# env.net
KiCad netlist of a schematic drawn in EAGLE
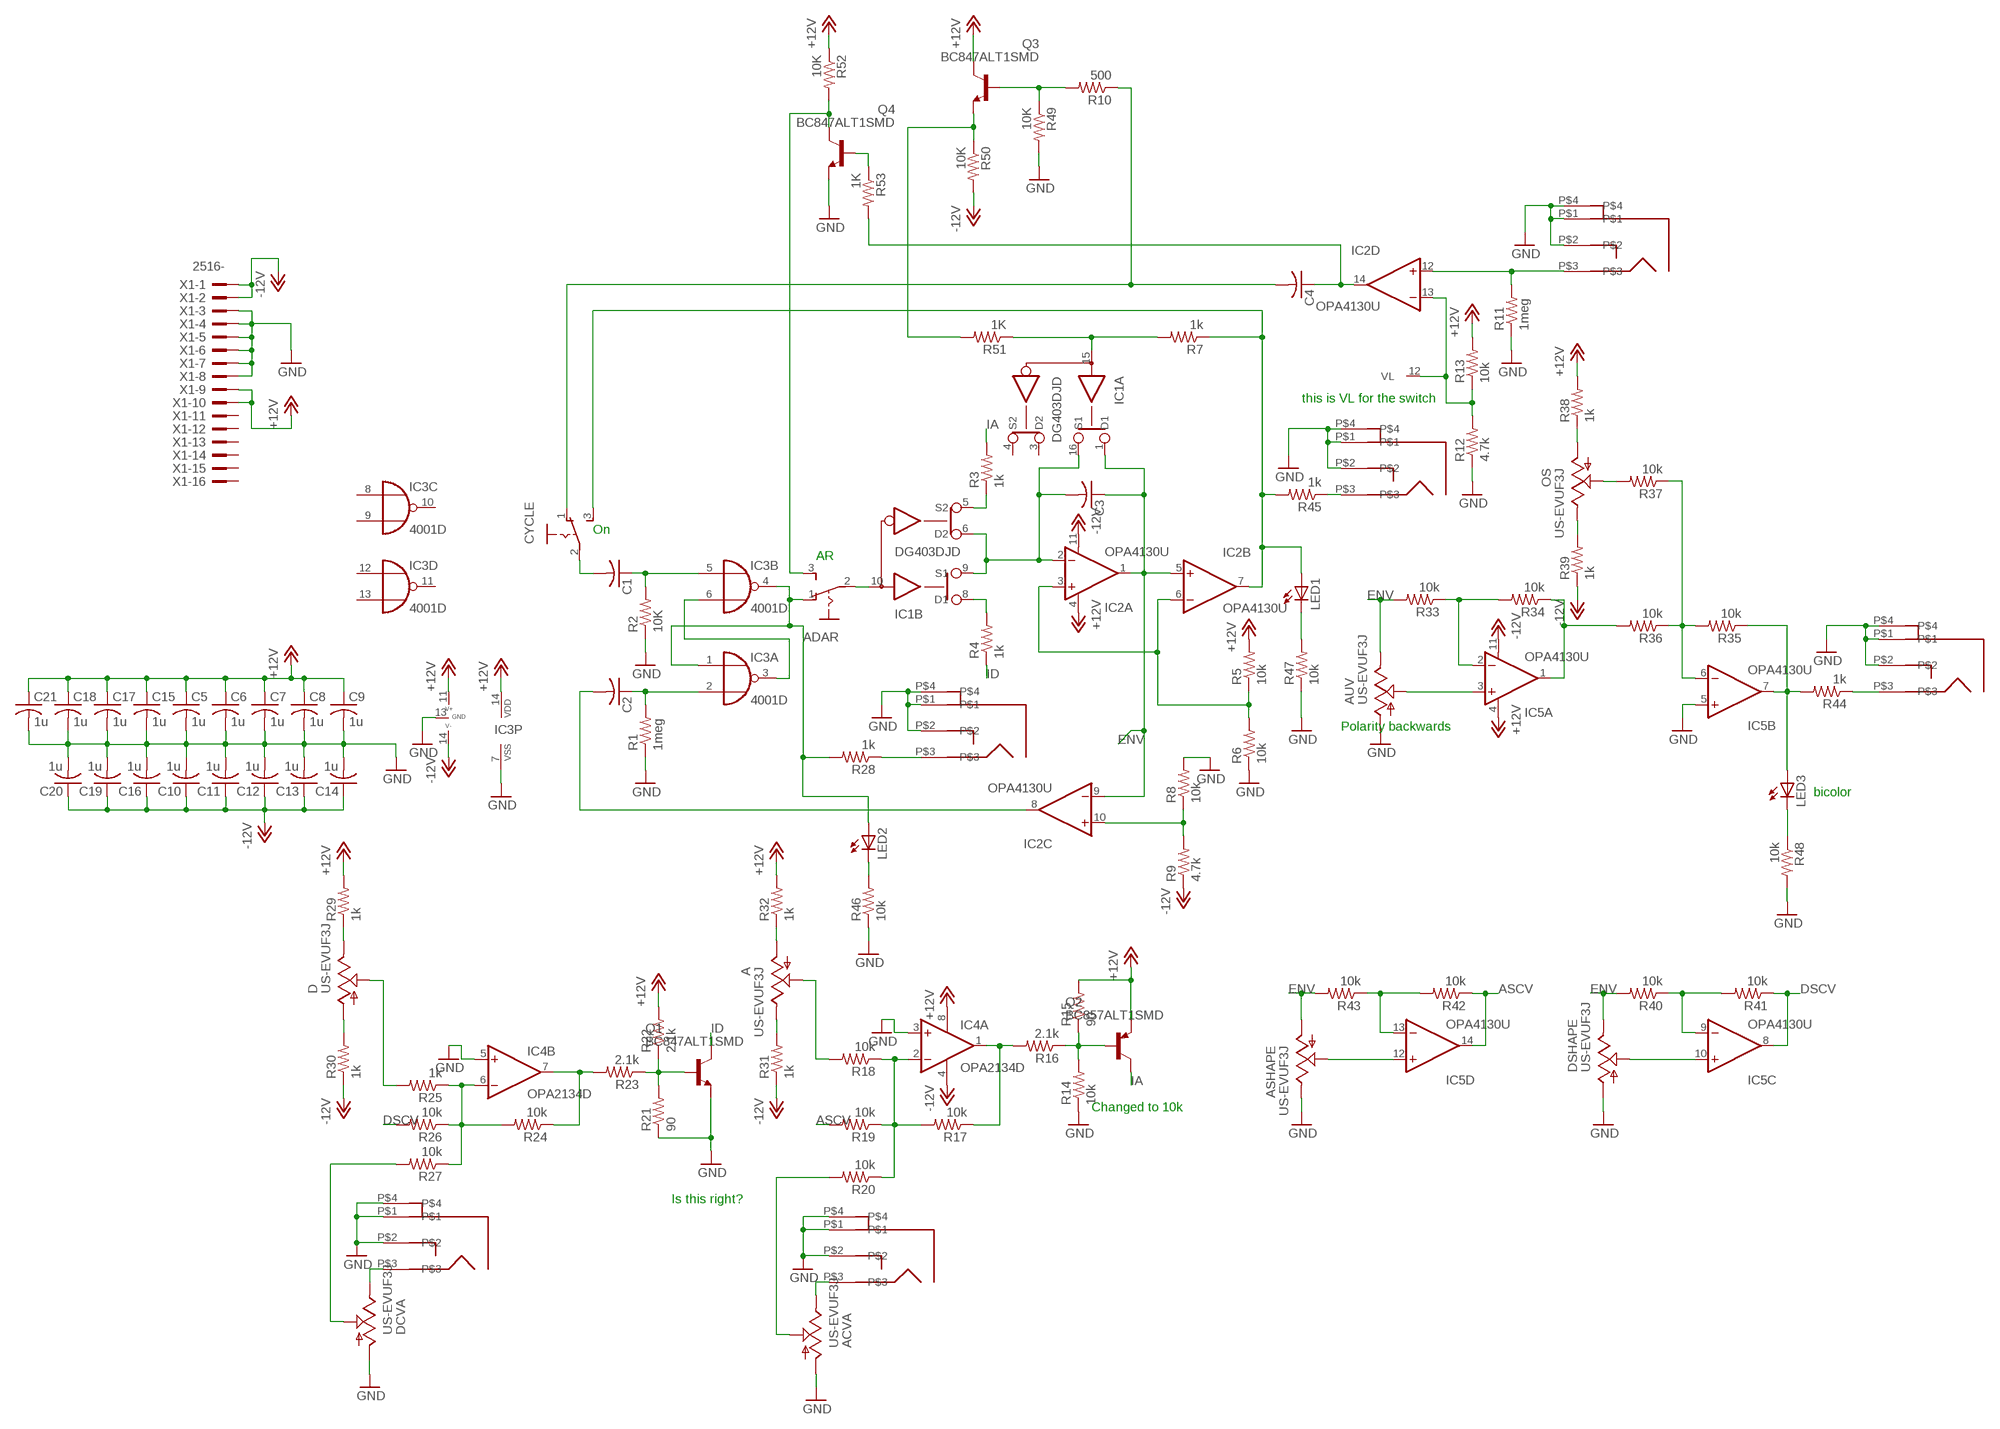
[diagram p0: schematic, sheet 1]

(export (version "E")
  (design (tool "Eeschema 10.0.6"))
  (components
    (comp (ref "A")
      (value "US-EVUF3J")
      (footprint "eagle-import:EVUFXJ")
      (libsource (lib "eagle-import") (part "US-EVUF3J"))
    )
    (comp (ref "ACV")
      (value "PJ301BM")
      (footprint "eagle-import:PJ301BM")
      (libsource (lib "eagle-import") (part "PJ301BM"))
    )
    (comp (ref "ACVA")
      (value "US-EVUF3J")
      (footprint "eagle-import:EVUFXJ")
      (libsource (lib "eagle-import") (part "US-EVUF3J"))
    )
    (comp (ref "ADAR")
      (value "255SB")
      (footprint "eagle-import:255SB")
      (libsource (lib "eagle-import") (part "255SB"))
    )
    (comp (ref "ASHAPE")
      (value "US-EVUF3J")
      (footprint "eagle-import:EVUFXJ")
      (libsource (lib "eagle-import") (part "US-EVUF3J"))
    )
    (comp (ref "AUV")
      (value "US-EVUF3J")
      (footprint "eagle-import:EVUFXJ")
      (libsource (lib "eagle-import") (part "US-EVUF3J"))
    )
    (comp (ref "C1")
      (value "C-USC0603")
      (footprint "eagle-import:C0603")
      (libsource (lib "eagle-import") (part "C-USC0603"))
    )
    (comp (ref "C2")
      (value "C-USC0603")
      (footprint "eagle-import:C0603")
      (libsource (lib "eagle-import") (part "C-USC0603"))
    )
    (comp (ref "C3")
      (value "C-USC0603")
      (footprint "eagle-import:C0603")
      (libsource (lib "eagle-import") (part "C-USC0603"))
    )
    (comp (ref "C4")
      (value "C-USC0603")
      (footprint "eagle-import:C0603")
      (libsource (lib "eagle-import") (part "C-USC0603"))
    )
    (comp (ref "C5")
      (value "1u")
      (footprint "eagle-import:C0603")
      (libsource (lib "eagle-import") (part "C-USC0603"))
    )
    (comp (ref "C6")
      (value "1u")
      (footprint "eagle-import:C0603")
      (libsource (lib "eagle-import") (part "C-USC0603"))
    )
    (comp (ref "C7")
      (value "1u")
      (footprint "eagle-import:C0603")
      (libsource (lib "eagle-import") (part "C-USC0603"))
    )
    (comp (ref "C8")
      (value "1u")
      (footprint "eagle-import:C0603")
      (libsource (lib "eagle-import") (part "C-USC0603"))
    )
    (comp (ref "C9")
      (value "1u")
      (footprint "eagle-import:C0603")
      (libsource (lib "eagle-import") (part "C-USC0603"))
    )
    (comp (ref "C10")
      (value "1u")
      (footprint "eagle-import:C0603")
      (libsource (lib "eagle-import") (part "C-USC0603"))
    )
    (comp (ref "C11")
      (value "1u")
      (footprint "eagle-import:C0603")
      (libsource (lib "eagle-import") (part "C-USC0603"))
    )
    (comp (ref "C12")
      (value "1u")
      (footprint "eagle-import:C0603")
      (libsource (lib "eagle-import") (part "C-USC0603"))
    )
    (comp (ref "C13")
      (value "1u")
      (footprint "eagle-import:C0603")
      (libsource (lib "eagle-import") (part "C-USC0603"))
    )
    (comp (ref "C14")
      (value "1u")
      (footprint "eagle-import:C0603")
      (libsource (lib "eagle-import") (part "C-USC0603"))
    )
    (comp (ref "C15")
      (value "1u")
      (footprint "eagle-import:C0603")
      (libsource (lib "eagle-import") (part "C-USC0603"))
    )
    (comp (ref "C16")
      (value "1u")
      (footprint "eagle-import:C0603")
      (libsource (lib "eagle-import") (part "C-USC0603"))
    )
    (comp (ref "C17")
      (value "1u")
      (footprint "eagle-import:C0603")
      (libsource (lib "eagle-import") (part "C-USC0603"))
    )
    (comp (ref "C18")
      (value "1u")
      (footprint "eagle-import:C0603")
      (libsource (lib "eagle-import") (part "C-USC0603"))
    )
    (comp (ref "C19")
      (value "1u")
      (footprint "eagle-import:C0603")
      (libsource (lib "eagle-import") (part "C-USC0603"))
    )
    (comp (ref "C20")
      (value "1u")
      (footprint "eagle-import:C0603")
      (libsource (lib "eagle-import") (part "C-USC0603"))
    )
    (comp (ref "C21")
      (value "1u")
      (footprint "eagle-import:C0603")
      (libsource (lib "eagle-import") (part "C-USC0603"))
    )
    (comp (ref "CVOUT")
      (value "PJ301BM")
      (footprint "eagle-import:PJ301BM")
      (libsource (lib "eagle-import") (part "PJ301BM"))
    )
    (comp (ref "CYCLE")
      (value "255SB")
      (footprint "eagle-import:255SB")
      (libsource (lib "eagle-import") (part "255SB"))
    )
    (comp (ref "D")
      (value "US-EVUF3J")
      (footprint "eagle-import:EVUFXJ")
      (libsource (lib "eagle-import") (part "US-EVUF3J"))
    )
    (comp (ref "DCV")
      (value "PJ301BM")
      (footprint "eagle-import:PJ301BM")
      (libsource (lib "eagle-import") (part "PJ301BM"))
    )
    (comp (ref "DCVA")
      (value "US-EVUF3J")
      (footprint "eagle-import:EVUFXJ")
      (libsource (lib "eagle-import") (part "US-EVUF3J"))
    )
    (comp (ref "DSHAPE")
      (value "US-EVUF3J")
      (footprint "eagle-import:EVUFXJ")
      (libsource (lib "eagle-import") (part "US-EVUF3J"))
    )
    (comp (ref "EOF")
      (value "PJ301BM")
      (footprint "eagle-import:PJ301BM")
      (libsource (lib "eagle-import") (part "PJ301BM"))
    )
    (comp (ref "EOR")
      (value "PJ301BM")
      (footprint "eagle-import:PJ301BM")
      (libsource (lib "eagle-import") (part "PJ301BM"))
    )
    (comp (ref "GATE")
      (value "PJ301BM")
      (footprint "eagle-import:PJ301BM")
      (libsource (lib "eagle-import") (part "PJ301BM"))
    )
    (comp (ref "IC1")
      (value "DG403DJD")
      (footprint "eagle-import:SO16")
      (libsource (lib "eagle-import") (part "DG403DJD"))
    )
    (comp (ref "IC2")
      (value "OPA4130U")
      (footprint "eagle-import:SO14")
      (fields (field (name "MF") "TEXAS INSTRUMENTS") (field (name "MPN") "OPA4130UA"))
      (libsource (lib "eagle-import") (part "OPA4130U"))
    )
    (comp (ref "IC3")
      (value "4001D")
      (footprint "eagle-import:SO14")
      (libsource (lib "eagle-import") (part "4001D"))
    )
    (comp (ref "IC4")
      (value "OPA2134D")
      (footprint "eagle-import:SOIC8")
      (libsource (lib "eagle-import") (part "OPA2134D"))
    )
    (comp (ref "IC5")
      (value "OPA4130U")
      (footprint "eagle-import:SO14")
      (fields (field (name "MF") "TEXAS INSTRUMENTS") (field (name "MPN") "OPA4130UA"))
      (libsource (lib "eagle-import") (part "OPA4130U"))
    )
    (comp (ref "LED1")
      (value "LED5MM")
      (footprint "eagle-import:LED5MM")
      (libsource (lib "eagle-import") (part "LED5MM"))
    )
    (comp (ref "LED2")
      (value "LED5MM")
      (footprint "eagle-import:LED5MM")
      (libsource (lib "eagle-import") (part "LED5MM"))
    )
    (comp (ref "LED3")
      (value "LED5MM")
      (footprint "eagle-import:LED5MM")
      (libsource (lib "eagle-import") (part "LED5MM"))
    )
    (comp (ref "OS")
      (value "US-EVUF3J")
      (footprint "eagle-import:EVUFXJ")
      (libsource (lib "eagle-import") (part "US-EVUF3J"))
    )
    (comp (ref "Q1")
      (value "BC847ALT1SMD")
      (footprint "eagle-import:SOT23")
      (libsource (lib "eagle-import") (part "BC847SMDALT1"))
    )
    (comp (ref "Q2")
      (value "BC857ALT1SMD")
      (footprint "eagle-import:SOT23-BEC")
      (libsource (lib "eagle-import") (part "BC857SMDALT1"))
    )
    (comp (ref "Q3")
      (value "BC847ALT1SMD")
      (footprint "eagle-import:SOT23")
      (libsource (lib "eagle-import") (part "BC847SMDALT1"))
    )
    (comp (ref "Q4")
      (value "BC847ALT1SMD")
      (footprint "eagle-import:SOT23")
      (libsource (lib "eagle-import") (part "BC847SMDALT1"))
    )
    (comp (ref "R1")
      (value "1meg")
      (footprint "eagle-import:R0603")
      (libsource (lib "eagle-import") (part "R-US_R0603"))
    )
    (comp (ref "R2")
      (value "10K")
      (footprint "eagle-import:R0603")
      (libsource (lib "eagle-import") (part "R-US_R0603"))
    )
    (comp (ref "R3")
      (value "1k")
      (footprint "eagle-import:R0603")
      (libsource (lib "eagle-import") (part "R-US_R0603"))
    )
    (comp (ref "R4")
      (value "1k")
      (footprint "eagle-import:R0603")
      (libsource (lib "eagle-import") (part "R-US_R0603"))
    )
    (comp (ref "R5")
      (value "10k")
      (footprint "eagle-import:R0603")
      (libsource (lib "eagle-import") (part "R-US_R0603"))
    )
    (comp (ref "R6")
      (value "10k")
      (footprint "eagle-import:R0603")
      (libsource (lib "eagle-import") (part "R-US_R0603"))
    )
    (comp (ref "R7")
      (value "1k")
      (footprint "eagle-import:R0603")
      (libsource (lib "eagle-import") (part "R-US_R0603"))
    )
    (comp (ref "R8")
      (value "10k")
      (footprint "eagle-import:R0603")
      (libsource (lib "eagle-import") (part "R-US_R0603"))
    )
    (comp (ref "R9")
      (value "4.7k")
      (footprint "eagle-import:R0603")
      (libsource (lib "eagle-import") (part "R-US_R0603"))
    )
    (comp (ref "R10")
      (value "500")
      (footprint "eagle-import:R0603")
      (libsource (lib "eagle-import") (part "R-US_R0603"))
    )
    (comp (ref "R11")
      (value "1meg")
      (footprint "eagle-import:R0603")
      (libsource (lib "eagle-import") (part "R-US_R0603"))
    )
    (comp (ref "R12")
      (value "4.7k")
      (footprint "eagle-import:R0603")
      (libsource (lib "eagle-import") (part "R-US_R0603"))
    )
    (comp (ref "R13")
      (value "10k")
      (footprint "eagle-import:R0603")
      (libsource (lib "eagle-import") (part "R-US_R0603"))
    )
    (comp (ref "R14")
      (value "10k")
      (footprint "eagle-import:R0603")
      (libsource (lib "eagle-import") (part "R-US_R0603"))
    )
    (comp (ref "R15")
      (value "90")
      (footprint "eagle-import:R0603")
      (libsource (lib "eagle-import") (part "R-US_R0603"))
    )
    (comp (ref "R16")
      (value "2.1k")
      (footprint "eagle-import:R0603")
      (libsource (lib "eagle-import") (part "R-US_R0603"))
    )
    (comp (ref "R17")
      (value "10k")
      (footprint "eagle-import:R0603")
      (libsource (lib "eagle-import") (part "R-US_R0603"))
    )
    (comp (ref "R18")
      (value "10k")
      (footprint "eagle-import:R0603")
      (libsource (lib "eagle-import") (part "R-US_R0603"))
    )
    (comp (ref "R19")
      (value "10k")
      (footprint "eagle-import:R0603")
      (libsource (lib "eagle-import") (part "R-US_R0603"))
    )
    (comp (ref "R20")
      (value "10k")
      (footprint "eagle-import:R0603")
      (libsource (lib "eagle-import") (part "R-US_R0603"))
    )
    (comp (ref "R21")
      (value "90")
      (footprint "eagle-import:R0603")
      (libsource (lib "eagle-import") (part "R-US_R0603"))
    )
    (comp (ref "R22")
      (value "2.1k")
      (footprint "eagle-import:R0603")
      (libsource (lib "eagle-import") (part "R-US_R0603"))
    )
    (comp (ref "R23")
      (value "2.1k")
      (footprint "eagle-import:R0603")
      (libsource (lib "eagle-import") (part "R-US_R0603"))
    )
    (comp (ref "R24")
      (value "10k")
      (footprint "eagle-import:R0603")
      (libsource (lib "eagle-import") (part "R-US_R0603"))
    )
    (comp (ref "R25")
      (value "1k")
      (footprint "eagle-import:R0603")
      (libsource (lib "eagle-import") (part "R-US_R0603"))
    )
    (comp (ref "R26")
      (value "10k")
      (footprint "eagle-import:R0603")
      (libsource (lib "eagle-import") (part "R-US_R0603"))
    )
    (comp (ref "R27")
      (value "10k")
      (footprint "eagle-import:R0603")
      (libsource (lib "eagle-import") (part "R-US_R0603"))
    )
    (comp (ref "R28")
      (value "1k")
      (footprint "eagle-import:R0603")
      (libsource (lib "eagle-import") (part "R-US_R0603"))
    )
    (comp (ref "R29")
      (value "1k")
      (footprint "eagle-import:R0603")
      (libsource (lib "eagle-import") (part "R-US_R0603"))
    )
    (comp (ref "R30")
      (value "1k")
      (footprint "eagle-import:R0603")
      (libsource (lib "eagle-import") (part "R-US_R0603"))
    )
    (comp (ref "R31")
      (value "1k")
      (footprint "eagle-import:R0603")
      (libsource (lib "eagle-import") (part "R-US_R0603"))
    )
    (comp (ref "R32")
      (value "1k")
      (footprint "eagle-import:R0603")
      (libsource (lib "eagle-import") (part "R-US_R0603"))
    )
    (comp (ref "R33")
      (value "10k")
      (footprint "eagle-import:R0603")
      (libsource (lib "eagle-import") (part "R-US_R0603"))
    )
    (comp (ref "R34")
      (value "10k")
      (footprint "eagle-import:R0603")
      (libsource (lib "eagle-import") (part "R-US_R0603"))
    )
    (comp (ref "R35")
      (value "10k")
      (footprint "eagle-import:R0603")
      (libsource (lib "eagle-import") (part "R-US_R0603"))
    )
    (comp (ref "R36")
      (value "10k")
      (footprint "eagle-import:R0603")
      (libsource (lib "eagle-import") (part "R-US_R0603"))
    )
    (comp (ref "R37")
      (value "10k")
      (footprint "eagle-import:R0603")
      (libsource (lib "eagle-import") (part "R-US_R0603"))
    )
    (comp (ref "R38")
      (value "1k")
      (footprint "eagle-import:R0603")
      (libsource (lib "eagle-import") (part "R-US_R0603"))
    )
    (comp (ref "R39")
      (value "1k")
      (footprint "eagle-import:R0603")
      (libsource (lib "eagle-import") (part "R-US_R0603"))
    )
    (comp (ref "R40")
      (value "10k")
      (footprint "eagle-import:R0603")
      (libsource (lib "eagle-import") (part "R-US_R0603"))
    )
    (comp (ref "R41")
      (value "10k")
      (footprint "eagle-import:R0603")
      (libsource (lib "eagle-import") (part "R-US_R0603"))
    )
    (comp (ref "R42")
      (value "10k")
      (footprint "eagle-import:R0603")
      (libsource (lib "eagle-import") (part "R-US_R0603"))
    )
    (comp (ref "R43")
      (value "10k")
      (footprint "eagle-import:R0603")
      (libsource (lib "eagle-import") (part "R-US_R0603"))
    )
    (comp (ref "R44")
      (value "1k")
      (footprint "eagle-import:R0603")
      (libsource (lib "eagle-import") (part "R-US_R0603"))
    )
    (comp (ref "R45")
      (value "1k")
      (footprint "eagle-import:R0603")
      (libsource (lib "eagle-import") (part "R-US_R0603"))
    )
    (comp (ref "R46")
      (value "10k")
      (footprint "eagle-import:R0603")
      (libsource (lib "eagle-import") (part "R-US_R0603"))
    )
    (comp (ref "R47")
      (value "10k")
      (footprint "eagle-import:R0603")
      (libsource (lib "eagle-import") (part "R-US_R0603"))
    )
    (comp (ref "R48")
      (value "10k")
      (footprint "eagle-import:R0603")
      (libsource (lib "eagle-import") (part "R-US_R0603"))
    )
    (comp (ref "R49")
      (value "10K")
      (footprint "eagle-import:R0603")
      (libsource (lib "eagle-import") (part "R-US_R0603"))
    )
    (comp (ref "R50")
      (value "10K")
      (footprint "eagle-import:R0603")
      (libsource (lib "eagle-import") (part "R-US_R0603"))
    )
    (comp (ref "R51")
      (value "1K")
      (footprint "eagle-import:R0603")
      (libsource (lib "eagle-import") (part "R-US_R0603"))
    )
    (comp (ref "R52")
      (value "10K")
      (footprint "eagle-import:R0603")
      (libsource (lib "eagle-import") (part "R-US_R0603"))
    )
    (comp (ref "R53")
      (value "1K")
      (footprint "eagle-import:R0603")
      (libsource (lib "eagle-import") (part "R-US_R0603"))
    )
    (comp (ref "X1")
      (value "2516-")
      (footprint "eagle-import:PAK100_2500-16")
      (libsource (lib "eagle-import") (part "2516-"))
    )
  )
  (nets
    (net (code "1") (name "+12V") (class "Default")
      (node (ref "C15") (pin "1") (pinfunction "1_1") (pintype "passive"))
      (node (ref "C17") (pin "1") (pinfunction "1_1") (pintype "passive"))
      (node (ref "C18") (pin "1") (pinfunction "1_1") (pintype "passive"))
      (node (ref "C21") (pin "1") (pinfunction "1_1") (pintype "passive"))
      (node (ref "C5") (pin "1") (pinfunction "1_1") (pintype "passive"))
      (node (ref "C6") (pin "1") (pinfunction "1_1") (pintype "passive"))
      (node (ref "C7") (pin "1") (pinfunction "1_1") (pintype "passive"))
      (node (ref "C8") (pin "1") (pinfunction "1_1") (pintype "passive"))
      (node (ref "C9") (pin "1") (pinfunction "1_1") (pintype "passive"))
      (node (ref "IC1") (pin "11") (pinfunction "V+_11") (pintype "power_in"))
      (node (ref "IC2") (pin "4") (pinfunction "V+_4") (pintype "power_in"))
      (node (ref "IC3") (pin "14") (pinfunction "VDD_14") (pintype "power_in"))
      (node (ref "IC4") (pin "8") (pinfunction "V+_8") (pintype "power_in"))
      (node (ref "IC5") (pin "4") (pinfunction "V+_4") (pintype "power_in"))
      (node (ref "Q2") (pin "E") (pinfunction "E_E") (pintype "passive"))
      (node (ref "Q3") (pin "3") (pinfunction "C_3") (pintype "passive"))
      (node (ref "R13") (pin "2") (pinfunction "2_2") (pintype "passive"))
      (node (ref "R15") (pin "2") (pinfunction "2_2") (pintype "passive"))
      (node (ref "R22") (pin "2") (pinfunction "2_2") (pintype "passive"))
      (node (ref "R29") (pin "2") (pinfunction "2_2") (pintype "passive"))
      (node (ref "R32") (pin "2") (pinfunction "2_2") (pintype "passive"))
      (node (ref "R38") (pin "2") (pinfunction "2_2") (pintype "passive"))
      (node (ref "R5") (pin "2") (pinfunction "2_2") (pintype "passive"))
      (node (ref "R52") (pin "1") (pinfunction "1_1") (pintype "passive"))
      (node (ref "X1") (pin "10") (pinfunction "KL_10") (pintype "passive"))
      (node (ref "X1") (pin "9") (pinfunction "KL_9") (pintype "passive"))
    )
    (net (code "2") (name "-12V") (class "Default")
      (node (ref "C10") (pin "1") (pinfunction "1_1") (pintype "passive"))
      (node (ref "C11") (pin "1") (pinfunction "1_1") (pintype "passive"))
      (node (ref "C12") (pin "1") (pinfunction "1_1") (pintype "passive"))
      (node (ref "C13") (pin "1") (pinfunction "1_1") (pintype "passive"))
      (node (ref "C14") (pin "1") (pinfunction "1_1") (pintype "passive"))
      (node (ref "C16") (pin "1") (pinfunction "1_1") (pintype "passive"))
      (node (ref "C19") (pin "1") (pinfunction "1_1") (pintype "passive"))
      (node (ref "C20") (pin "1") (pinfunction "1_1") (pintype "passive"))
      (node (ref "IC1") (pin "14") (pinfunction "V-_14") (pintype "power_in"))
      (node (ref "IC2") (pin "11") (pinfunction "V-_11") (pintype "power_in"))
      (node (ref "IC4") (pin "4") (pinfunction "V-_4") (pintype "power_in"))
      (node (ref "IC5") (pin "11") (pinfunction "V-_11") (pintype "power_in"))
      (node (ref "R30") (pin "1") (pinfunction "1_1") (pintype "passive"))
      (node (ref "R31") (pin "1") (pinfunction "1_1") (pintype "passive"))
      (node (ref "R39") (pin "1") (pinfunction "1_1") (pintype "passive"))
      (node (ref "R50") (pin "2") (pinfunction "2_2") (pintype "passive"))
      (node (ref "R9") (pin "1") (pinfunction "1_1") (pintype "passive"))
      (node (ref "X1") (pin "1") (pinfunction "KL_1") (pintype "passive"))
      (node (ref "X1") (pin "2") (pinfunction "KL_2") (pintype "passive"))
    )
    (net (code "3") (name "/ASCV") (class "Default")
      (node (ref "IC5") (pin "14") (pinfunction "OUT_14") (pintype "output"))
      (node (ref "R19") (pin "2") (pinfunction "2_2") (pintype "passive"))
      (node (ref "R42") (pin "1") (pinfunction "1_1") (pintype "passive"))
    )
    (net (code "4") (name "/DSCV") (class "Default")
      (node (ref "IC5") (pin "8") (pinfunction "OUT_8") (pintype "output"))
      (node (ref "R26") (pin "2") (pinfunction "2_2") (pintype "passive"))
      (node (ref "R41") (pin "1") (pinfunction "1_1") (pintype "passive"))
    )
    (net (code "5") (name "/ENV") (class "Default")
      (node (ref "ASHAPE") (pin "1") (pinfunction "A_1") (pintype "passive"))
      (node (ref "AUV") (pin "3") (pinfunction "E_3") (pintype "passive"))
      (node (ref "C3") (pin "1") (pinfunction "1_1") (pintype "passive"))
      (node (ref "DSHAPE") (pin "3") (pinfunction "E_3") (pintype "passive"))
      (node (ref "IC1") (pin "1") (pinfunction "D1_1") (pintype "bidirectional"))
      (node (ref "IC2") (pin "1") (pinfunction "OUT_1") (pintype "output"))
      (node (ref "IC2") (pin "5") (pinfunction "+IN_5") (pintype "input"))
      (node (ref "IC2") (pin "9") (pinfunction "-IN_9") (pintype "input"))
      (node (ref "R33") (pin "2") (pinfunction "2_2") (pintype "passive"))
      (node (ref "R40") (pin "2") (pinfunction "2_2") (pintype "passive"))
      (node (ref "R43") (pin "2") (pinfunction "2_2") (pintype "passive"))
    )
    (net (code "6") (name "/IA") (class "Default")
      (node (ref "Q2") (pin "C") (pinfunction "C_C") (pintype "passive"))
      (node (ref "R3") (pin "2") (pinfunction "2_2") (pintype "passive"))
    )
    (net (code "7") (name "/ID") (class "Default")
      (node (ref "Q1") (pin "3") (pinfunction "C_3") (pintype "passive"))
      (node (ref "R4") (pin "1") (pinfunction "1_1") (pintype "passive"))
    )
    (net (code "8") (name "GND") (class "Default")
      (node (ref "ACV") (pin "P$1") (pinfunction "P$1_P$1") (pintype "bidirectional"))
      (node (ref "ACV") (pin "P$2") (pinfunction "P$2_P$2") (pintype "bidirectional"))
      (node (ref "ACV") (pin "P$4") (pinfunction "P$4_P$4") (pintype "bidirectional"))
      (node (ref "ACVA") (pin "1") (pinfunction "A_1") (pintype "passive"))
      (node (ref "ASHAPE") (pin "3") (pinfunction "E_3") (pintype "passive"))
      (node (ref "AUV") (pin "1") (pinfunction "A_1") (pintype "passive"))
      (node (ref "C10") (pin "2") (pinfunction "2_2") (pintype "passive"))
      (node (ref "C11") (pin "2") (pinfunction "2_2") (pintype "passive"))
      (node (ref "C12") (pin "2") (pinfunction "2_2") (pintype "passive"))
      (node (ref "C13") (pin "2") (pinfunction "2_2") (pintype "passive"))
      (node (ref "C14") (pin "2") (pinfunction "2_2") (pintype "passive"))
      (node (ref "C15") (pin "2") (pinfunction "2_2") (pintype "passive"))
      (node (ref "C16") (pin "2") (pinfunction "2_2") (pintype "passive"))
      (node (ref "C17") (pin "2") (pinfunction "2_2") (pintype "passive"))
      (node (ref "C18") (pin "2") (pinfunction "2_2") (pintype "passive"))
      (node (ref "C19") (pin "2") (pinfunction "2_2") (pintype "passive"))
      (node (ref "C20") (pin "2") (pinfunction "2_2") (pintype "passive"))
      (node (ref "C21") (pin "2") (pinfunction "2_2") (pintype "passive"))
      (node (ref "C5") (pin "2") (pinfunction "2_2") (pintype "passive"))
      (node (ref "C6") (pin "2") (pinfunction "2_2") (pintype "passive"))
      (node (ref "C7") (pin "2") (pinfunction "2_2") (pintype "passive"))
      (node (ref "C8") (pin "2") (pinfunction "2_2") (pintype "passive"))
      (node (ref "C9") (pin "2") (pinfunction "2_2") (pintype "passive"))
      (node (ref "CVOUT") (pin "P$1") (pinfunction "P$1_P$1") (pintype "bidirectional"))
      (node (ref "CVOUT") (pin "P$2") (pinfunction "P$2_P$2") (pintype "bidirectional"))
      (node (ref "CVOUT") (pin "P$4") (pinfunction "P$4_P$4") (pintype "bidirectional"))
      (node (ref "DCV") (pin "P$1") (pinfunction "P$1_P$1") (pintype "bidirectional"))
      (node (ref "DCV") (pin "P$2") (pinfunction "P$2_P$2") (pintype "bidirectional"))
      (node (ref "DCV") (pin "P$4") (pinfunction "P$4_P$4") (pintype "bidirectional"))
      (node (ref "DCVA") (pin "1") (pinfunction "A_1") (pintype "passive"))
      (node (ref "DSHAPE") (pin "1") (pinfunction "A_1") (pintype "passive"))
      (node (ref "EOF") (pin "P$1") (pinfunction "P$1_P$1") (pintype "bidirectional"))
      (node (ref "EOF") (pin "P$2") (pinfunction "P$2_P$2") (pintype "bidirectional"))
      (node (ref "EOF") (pin "P$4") (pinfunction "P$4_P$4") (pintype "bidirectional"))
      (node (ref "EOR") (pin "P$1") (pinfunction "P$1_P$1") (pintype "bidirectional"))
      (node (ref "EOR") (pin "P$2") (pinfunction "P$2_P$2") (pintype "bidirectional"))
      (node (ref "EOR") (pin "P$4") (pinfunction "P$4_P$4") (pintype "bidirectional"))
      (node (ref "GATE") (pin "P$1") (pinfunction "P$1_P$1") (pintype "bidirectional"))
      (node (ref "GATE") (pin "P$2") (pinfunction "P$2_P$2") (pintype "bidirectional"))
      (node (ref "GATE") (pin "P$4") (pinfunction "P$4_P$4") (pintype "bidirectional"))
      (node (ref "IC1") (pin "13") (pinfunction "GND_13") (pintype "power_in"))
      (node (ref "IC3") (pin "7") (pinfunction "VSS_7") (pintype "power_in"))
      (node (ref "IC4") (pin "3") (pinfunction "+IN_3") (pintype "input"))
      (node (ref "IC4") (pin "5") (pinfunction "+IN_5") (pintype "input"))
      (node (ref "IC5") (pin "5") (pinfunction "+IN_5") (pintype "input"))
      (node (ref "Q1") (pin "2") (pinfunction "E_2") (pintype "passive"))
      (node (ref "Q4") (pin "2") (pinfunction "E_2") (pintype "passive"))
      (node (ref "R1") (pin "1") (pinfunction "1_1") (pintype "passive"))
      (node (ref "R11") (pin "1") (pinfunction "1_1") (pintype "passive"))
      (node (ref "R12") (pin "1") (pinfunction "1_1") (pintype "passive"))
      (node (ref "R14") (pin "1") (pinfunction "1_1") (pintype "passive"))
      (node (ref "R2") (pin "1") (pinfunction "1_1") (pintype "passive"))
      (node (ref "R21") (pin "1") (pinfunction "1_1") (pintype "passive"))
      (node (ref "R46") (pin "1") (pinfunction "1_1") (pintype "passive"))
      (node (ref "R47") (pin "1") (pinfunction "1_1") (pintype "passive"))
      (node (ref "R48") (pin "2") (pinfunction "2_2") (pintype "passive"))
      (node (ref "R49") (pin "2") (pinfunction "2_2") (pintype "passive"))
      (node (ref "R6") (pin "1") (pinfunction "1_1") (pintype "passive"))
      (node (ref "R8") (pin "2") (pinfunction "2_2") (pintype "passive"))
      (node (ref "X1") (pin "3") (pinfunction "KL_3") (pintype "passive"))
      (node (ref "X1") (pin "4") (pinfunction "KL_4") (pintype "passive"))
      (node (ref "X1") (pin "5") (pinfunction "KL_5") (pintype "passive"))
      (node (ref "X1") (pin "6") (pinfunction "KL_6") (pintype "passive"))
      (node (ref "X1") (pin "7") (pinfunction "KL_7") (pintype "passive"))
      (node (ref "X1") (pin "8") (pinfunction "KL_8") (pintype "passive"))
    )
    (net (code "9") (name "Net-(A-A)") (class "Default")
      (node (ref "A") (pin "1") (pinfunction "A_1") (pintype "passive"))
      (node (ref "R32") (pin "1") (pinfunction "1_1") (pintype "passive"))
    )
    (net (code "10") (name "Net-(A-E)") (class "Default")
      (node (ref "A") (pin "3") (pinfunction "E_3") (pintype "passive"))
      (node (ref "R31") (pin "2") (pinfunction "2_2") (pintype "passive"))
    )
    (net (code "11") (name "Net-(A-S)") (class "Default")
      (node (ref "A") (pin "2") (pinfunction "S_2") (pintype "passive"))
      (node (ref "R18") (pin "2") (pinfunction "2_2") (pintype "passive"))
    )
    (net (code "12") (name "Net-(ACVA-E)") (class "Default")
      (node (ref "ACV") (pin "P$3") (pinfunction "P$3_P$3") (pintype "bidirectional"))
      (node (ref "ACVA") (pin "3") (pinfunction "E_3") (pintype "passive"))
    )
    (net (code "13") (name "Net-(ACVA-S)") (class "Default")
      (node (ref "ACVA") (pin "2") (pinfunction "S_2") (pintype "passive"))
      (node (ref "R20") (pin "2") (pinfunction "2_2") (pintype "passive"))
    )
    (net (code "14") (name "Net-(ADAR-O)") (class "Default")
      (node (ref "ADAR") (pin "1") (pinfunction "O_1") (pintype "passive"))
      (node (ref "IC3") (pin "1") (pinfunction "I0_1") (pintype "input"))
      (node (ref "IC3") (pin "4") (pinfunction "O_4") (pintype "output"))
      (node (ref "LED2") (pin "A") (pinfunction "A_A") (pintype "passive"))
      (node (ref "R28") (pin "2") (pinfunction "2_2") (pintype "passive"))
    )
    (net (code "15") (name "Net-(ADAR-P)") (class "Default")
      (node (ref "ADAR") (pin "2") (pinfunction "P_2") (pintype "passive"))
      (node (ref "IC1") (pin "10") (pinfunction "IN_10") (pintype "input"))
    )
    (net (code "16") (name "Net-(ADAR-S)") (class "Default")
      (node (ref "ADAR") (pin "3") (pinfunction "S_3") (pintype "passive"))
      (node (ref "Q4") (pin "3") (pinfunction "C_3") (pintype "passive"))
      (node (ref "R52") (pin "2") (pinfunction "2_2") (pintype "passive"))
    )
    (net (code "17") (name "Net-(ASHAPE-S)") (class "Default")
      (node (ref "ASHAPE") (pin "2") (pinfunction "S_2") (pintype "passive"))
      (node (ref "IC5") (pin "12") (pinfunction "+IN_12") (pintype "input"))
    )
    (net (code "18") (name "Net-(AUV-S)") (class "Default")
      (node (ref "AUV") (pin "2") (pinfunction "S_2") (pintype "passive"))
      (node (ref "IC5") (pin "3") (pinfunction "+IN_3") (pintype "input"))
    )
    (net (code "19") (name "Net-(CVOUT-PadP$3)") (class "Default")
      (node (ref "CVOUT") (pin "P$3") (pinfunction "P$3_P$3") (pintype "bidirectional"))
      (node (ref "R44") (pin "1") (pinfunction "1_1") (pintype "passive"))
    )
    (net (code "20") (name "Net-(CYCLE-O)") (class "Default")
      (node (ref "C4") (pin "2") (pinfunction "2_2") (pintype "passive"))
      (node (ref "CYCLE") (pin "1") (pinfunction "O_1") (pintype "passive"))
      (node (ref "R10") (pin "1") (pinfunction "1_1") (pintype "passive"))
    )
    (net (code "21") (name "Net-(CYCLE-P)") (class "Default")
      (node (ref "C1") (pin "2") (pinfunction "2_2") (pintype "passive"))
      (node (ref "CYCLE") (pin "2") (pinfunction "P_2") (pintype "passive"))
    )
    (net (code "22") (name "Net-(CYCLE-S)") (class "Default")
      (node (ref "CYCLE") (pin "3") (pinfunction "S_3") (pintype "passive"))
      (node (ref "IC2") (pin "7") (pinfunction "OUT_7") (pintype "output"))
      (node (ref "LED1") (pin "A") (pinfunction "A_A") (pintype "passive"))
      (node (ref "R45") (pin "2") (pinfunction "2_2") (pintype "passive"))
      (node (ref "R7") (pin "1") (pinfunction "1_1") (pintype "passive"))
    )
    (net (code "23") (name "Net-(D-A)") (class "Default")
      (node (ref "D") (pin "1") (pinfunction "A_1") (pintype "passive"))
      (node (ref "R30") (pin "2") (pinfunction "2_2") (pintype "passive"))
    )
    (net (code "24") (name "Net-(D-E)") (class "Default")
      (node (ref "D") (pin "3") (pinfunction "E_3") (pintype "passive"))
      (node (ref "R29") (pin "1") (pinfunction "1_1") (pintype "passive"))
    )
    (net (code "25") (name "Net-(D-S)") (class "Default")
      (node (ref "D") (pin "2") (pinfunction "S_2") (pintype "passive"))
      (node (ref "R25") (pin "2") (pinfunction "2_2") (pintype "passive"))
    )
    (net (code "26") (name "Net-(DCVA-E)") (class "Default")
      (node (ref "DCV") (pin "P$3") (pinfunction "P$3_P$3") (pintype "bidirectional"))
      (node (ref "DCVA") (pin "3") (pinfunction "E_3") (pintype "passive"))
    )
    (net (code "27") (name "Net-(DCVA-S)") (class "Default")
      (node (ref "DCVA") (pin "2") (pinfunction "S_2") (pintype "passive"))
      (node (ref "R27") (pin "2") (pinfunction "2_2") (pintype "passive"))
    )
    (net (code "28") (name "Net-(DSHAPE-S)") (class "Default")
      (node (ref "DSHAPE") (pin "2") (pinfunction "S_2") (pintype "passive"))
      (node (ref "IC5") (pin "10") (pinfunction "+IN_10") (pintype "input"))
    )
    (net (code "29") (name "Net-(EOF-PadP$3)") (class "Default")
      (node (ref "EOF") (pin "P$3") (pinfunction "P$3_P$3") (pintype "bidirectional"))
      (node (ref "R45") (pin "1") (pinfunction "1_1") (pintype "passive"))
    )
    (net (code "30") (name "Net-(EOR-PadP$3)") (class "Default")
      (node (ref "EOR") (pin "P$3") (pinfunction "P$3_P$3") (pintype "bidirectional"))
      (node (ref "R28") (pin "1") (pinfunction "1_1") (pintype "passive"))
    )
    (net (code "31") (name "Net-(IC1A-IN)") (class "Default")
      (node (ref "IC1") (pin "15") (pinfunction "IN_15") (pintype "input"))
      (node (ref "R51") (pin "1") (pinfunction "1_1") (pintype "passive"))
      (node (ref "R7") (pin "2") (pinfunction "2_2") (pintype "passive"))
    )
    (net (code "32") (name "Net-(IC1A-S1)") (class "Default")
      (node (ref "C3") (pin "2") (pinfunction "2_2") (pintype "passive"))
      (node (ref "IC1") (pin "16") (pinfunction "S1_16") (pintype "bidirectional"))
      (node (ref "IC1") (pin "6") (pinfunction "D2_6") (pintype "bidirectional"))
      (node (ref "IC1") (pin "9") (pinfunction "S1_9") (pintype "bidirectional"))
      (node (ref "IC2") (pin "2") (pinfunction "-IN_2") (pintype "input"))
    )
    (net (code "33") (name "Net-(IC1B-D1)") (class "Default")
      (node (ref "IC1") (pin "8") (pinfunction "D1_8") (pintype "bidirectional"))
      (node (ref "R4") (pin "2") (pinfunction "2_2") (pintype "passive"))
    )
    (net (code "34") (name "Net-(IC1B-S2)") (class "Default")
      (node (ref "IC1") (pin "5") (pinfunction "S2_5") (pintype "bidirectional"))
      (node (ref "R3") (pin "1") (pinfunction "1_1") (pintype "passive"))
    )
    (net (code "35") (name "Net-(IC1D-VL)") (class "Default")
      (node (ref "IC1") (pin "12") (pinfunction "VL_12") (pintype "input"))
      (node (ref "IC2") (pin "13") (pinfunction "-IN_13") (pintype "input"))
      (node (ref "R12") (pin "2") (pinfunction "2_2") (pintype "passive"))
      (node (ref "R13") (pin "1") (pinfunction "1_1") (pintype "passive"))
    )
    (net (code "36") (name "Net-(IC2A-+IN)") (class "Default")
      (node (ref "IC2") (pin "3") (pinfunction "+IN_3") (pintype "input"))
      (node (ref "IC2") (pin "6") (pinfunction "-IN_6") (pintype "input"))
      (node (ref "R5") (pin "1") (pinfunction "1_1") (pintype "passive"))
      (node (ref "R6") (pin "2") (pinfunction "2_2") (pintype "passive"))
    )
    (net (code "37") (name "Net-(IC2C-+IN)") (class "Default")
      (node (ref "IC2") (pin "10") (pinfunction "+IN_10") (pintype "input"))
      (node (ref "R8") (pin "1") (pinfunction "1_1") (pintype "passive"))
      (node (ref "R9") (pin "2") (pinfunction "2_2") (pintype "passive"))
    )
    (net (code "38") (name "Net-(IC2C-OUT)") (class "Default")
      (node (ref "C2") (pin "2") (pinfunction "2_2") (pintype "passive"))
      (node (ref "IC2") (pin "8") (pinfunction "OUT_8") (pintype "output"))
    )
    (net (code "39") (name "Net-(IC2D-+IN)") (class "Default")
      (node (ref "GATE") (pin "P$3") (pinfunction "P$3_P$3") (pintype "bidirectional"))
      (node (ref "IC2") (pin "12") (pinfunction "+IN_12") (pintype "input"))
      (node (ref "R11") (pin "2") (pinfunction "2_2") (pintype "passive"))
    )
    (net (code "40") (name "Net-(IC2D-OUT)") (class "Default")
      (node (ref "C4") (pin "1") (pinfunction "1_1") (pintype "passive"))
      (node (ref "IC2") (pin "14") (pinfunction "OUT_14") (pintype "output"))
      (node (ref "R53") (pin "2") (pinfunction "2_2") (pintype "passive"))
    )
    (net (code "41") (name "Net-(IC3A-I1)") (class "Default")
      (node (ref "C2") (pin "1") (pinfunction "1_1") (pintype "passive"))
      (node (ref "IC3") (pin "2") (pinfunction "I1_2") (pintype "input"))
      (node (ref "R1") (pin "2") (pinfunction "2_2") (pintype "passive"))
    )
    (net (code "42") (name "Net-(IC3A-O)") (class "Default")
      (node (ref "IC3") (pin "3") (pinfunction "O_3") (pintype "output"))
      (node (ref "IC3") (pin "6") (pinfunction "I1_6") (pintype "input"))
    )
    (net (code "43") (name "Net-(IC3B-I0)") (class "Default")
      (node (ref "C1") (pin "1") (pinfunction "1_1") (pintype "passive"))
      (node (ref "IC3") (pin "5") (pinfunction "I0_5") (pintype "input"))
      (node (ref "R2") (pin "2") (pinfunction "2_2") (pintype "passive"))
    )
    (net (code "44") (name "Net-(IC4A--IN)") (class "Default")
      (node (ref "IC4") (pin "2") (pinfunction "-IN_2") (pintype "input"))
      (node (ref "R17") (pin "2") (pinfunction "2_2") (pintype "passive"))
      (node (ref "R18") (pin "1") (pinfunction "1_1") (pintype "passive"))
      (node (ref "R19") (pin "1") (pinfunction "1_1") (pintype "passive"))
      (node (ref "R20") (pin "1") (pinfunction "1_1") (pintype "passive"))
    )
    (net (code "45") (name "Net-(IC4A-OUT)") (class "Default")
      (node (ref "IC4") (pin "1") (pinfunction "OUT_1") (pintype "output"))
      (node (ref "R16") (pin "2") (pinfunction "2_2") (pintype "passive"))
      (node (ref "R17") (pin "1") (pinfunction "1_1") (pintype "passive"))
    )
    (net (code "46") (name "Net-(IC4B--IN)") (class "Default")
      (node (ref "IC4") (pin "6") (pinfunction "-IN_6") (pintype "input"))
      (node (ref "R24") (pin "2") (pinfunction "2_2") (pintype "passive"))
      (node (ref "R25") (pin "1") (pinfunction "1_1") (pintype "passive"))
      (node (ref "R26") (pin "1") (pinfunction "1_1") (pintype "passive"))
      (node (ref "R27") (pin "1") (pinfunction "1_1") (pintype "passive"))
    )
    (net (code "47") (name "Net-(IC4B-OUT)") (class "Default")
      (node (ref "IC4") (pin "7") (pinfunction "OUT_7") (pintype "output"))
      (node (ref "R23") (pin "2") (pinfunction "2_2") (pintype "passive"))
      (node (ref "R24") (pin "1") (pinfunction "1_1") (pintype "passive"))
    )
    (net (code "48") (name "Net-(IC5A--IN)") (class "Default")
      (node (ref "IC5") (pin "2") (pinfunction "-IN_2") (pintype "input"))
      (node (ref "R33") (pin "1") (pinfunction "1_1") (pintype "passive"))
      (node (ref "R34") (pin "2") (pinfunction "2_2") (pintype "passive"))
    )
    (net (code "49") (name "Net-(IC5A-OUT)") (class "Default")
      (node (ref "IC5") (pin "1") (pinfunction "OUT_1") (pintype "output"))
      (node (ref "R34") (pin "1") (pinfunction "1_1") (pintype "passive"))
      (node (ref "R36") (pin "2") (pinfunction "2_2") (pintype "passive"))
    )
    (net (code "50") (name "Net-(IC5B--IN)") (class "Default")
      (node (ref "IC5") (pin "6") (pinfunction "-IN_6") (pintype "input"))
      (node (ref "R35") (pin "2") (pinfunction "2_2") (pintype "passive"))
      (node (ref "R36") (pin "1") (pinfunction "1_1") (pintype "passive"))
      (node (ref "R37") (pin "1") (pinfunction "1_1") (pintype "passive"))
    )
    (net (code "51") (name "Net-(IC5B-OUT)") (class "Default")
      (node (ref "IC5") (pin "7") (pinfunction "OUT_7") (pintype "output"))
      (node (ref "LED3") (pin "A") (pinfunction "A_A") (pintype "passive"))
      (node (ref "R35") (pin "1") (pinfunction "1_1") (pintype "passive"))
      (node (ref "R44") (pin "2") (pinfunction "2_2") (pintype "passive"))
    )
    (net (code "52") (name "Net-(IC5C--IN)") (class "Default")
      (node (ref "IC5") (pin "9") (pinfunction "-IN_9") (pintype "input"))
      (node (ref "R40") (pin "1") (pinfunction "1_1") (pintype "passive"))
      (node (ref "R41") (pin "2") (pinfunction "2_2") (pintype "passive"))
    )
    (net (code "53") (name "Net-(IC5D--IN)") (class "Default")
      (node (ref "IC5") (pin "13") (pinfunction "-IN_13") (pintype "input"))
      (node (ref "R42") (pin "2") (pinfunction "2_2") (pintype "passive"))
      (node (ref "R43") (pin "1") (pinfunction "1_1") (pintype "passive"))
    )
    (net (code "54") (name "Net-(LED1-C)") (class "Default")
      (node (ref "LED1") (pin "K") (pinfunction "C_K") (pintype "passive"))
      (node (ref "R47") (pin "2") (pinfunction "2_2") (pintype "passive"))
    )
    (net (code "55") (name "Net-(LED2-C)") (class "Default")
      (node (ref "LED2") (pin "K") (pinfunction "C_K") (pintype "passive"))
      (node (ref "R46") (pin "2") (pinfunction "2_2") (pintype "passive"))
    )
    (net (code "56") (name "Net-(LED3-C)") (class "Default")
      (node (ref "LED3") (pin "K") (pinfunction "C_K") (pintype "passive"))
      (node (ref "R48") (pin "1") (pinfunction "1_1") (pintype "passive"))
    )
    (net (code "57") (name "Net-(OS-A)") (class "Default")
      (node (ref "OS") (pin "1") (pinfunction "A_1") (pintype "passive"))
      (node (ref "R38") (pin "1") (pinfunction "1_1") (pintype "passive"))
    )
    (net (code "58") (name "Net-(OS-E)") (class "Default")
      (node (ref "OS") (pin "3") (pinfunction "E_3") (pintype "passive"))
      (node (ref "R39") (pin "2") (pinfunction "2_2") (pintype "passive"))
    )
    (net (code "59") (name "Net-(OS-S)") (class "Default")
      (node (ref "OS") (pin "2") (pinfunction "S_2") (pintype "passive"))
      (node (ref "R37") (pin "2") (pinfunction "2_2") (pintype "passive"))
    )
    (net (code "60") (name "Net-(Q1-B)") (class "Default")
      (node (ref "Q1") (pin "1") (pinfunction "B_1") (pintype "passive"))
      (node (ref "R21") (pin "2") (pinfunction "2_2") (pintype "passive"))
      (node (ref "R22") (pin "1") (pinfunction "1_1") (pintype "passive"))
      (node (ref "R23") (pin "1") (pinfunction "1_1") (pintype "passive"))
    )
    (net (code "61") (name "Net-(Q2-PadB)") (class "Default")
      (node (ref "Q2") (pin "B") (pinfunction "B_B") (pintype "passive"))
      (node (ref "R14") (pin "2") (pinfunction "2_2") (pintype "passive"))
      (node (ref "R15") (pin "1") (pinfunction "1_1") (pintype "passive"))
      (node (ref "R16") (pin "1") (pinfunction "1_1") (pintype "passive"))
    )
    (net (code "62") (name "Net-(Q3-B)") (class "Default")
      (node (ref "Q3") (pin "1") (pinfunction "B_1") (pintype "passive"))
      (node (ref "R10") (pin "2") (pinfunction "2_2") (pintype "passive"))
      (node (ref "R49") (pin "1") (pinfunction "1_1") (pintype "passive"))
    )
    (net (code "63") (name "Net-(Q3-E)") (class "Default")
      (node (ref "Q3") (pin "2") (pinfunction "E_2") (pintype "passive"))
      (node (ref "R50") (pin "1") (pinfunction "1_1") (pintype "passive"))
      (node (ref "R51") (pin "2") (pinfunction "2_2") (pintype "passive"))
    )
    (net (code "64") (name "Net-(Q4-B)") (class "Default")
      (node (ref "Q4") (pin "1") (pinfunction "B_1") (pintype "passive"))
      (node (ref "R53") (pin "1") (pinfunction "1_1") (pintype "passive"))
    )
    (net (code "65") (name "unconnected-(IC1A-D2-Pad3)") (class "Default")
      (node (ref "IC1") (pin "3") (pinfunction "D2_3") (pintype "bidirectional"))
    )
    (net (code "66") (name "unconnected-(IC1A-S2-Pad4)") (class "Default")
      (node (ref "IC1") (pin "4") (pinfunction "S2_4") (pintype "bidirectional"))
    )
    (net (code "67") (name "unconnected-(IC3C-I0-Pad8)") (class "Default")
      (node (ref "IC3") (pin "8") (pinfunction "I0_8") (pintype "input"))
    )
    (net (code "68") (name "unconnected-(IC3C-I1-Pad9)") (class "Default")
      (node (ref "IC3") (pin "9") (pinfunction "I1_9") (pintype "input"))
    )
    (net (code "69") (name "unconnected-(IC3C-O-Pad10)") (class "Default")
      (node (ref "IC3") (pin "10") (pinfunction "O_10") (pintype "output"))
    )
    (net (code "70") (name "unconnected-(IC3D-I0-Pad12)") (class "Default")
      (node (ref "IC3") (pin "12") (pinfunction "I0_12") (pintype "input"))
    )
    (net (code "71") (name "unconnected-(IC3D-I1-Pad13)") (class "Default")
      (node (ref "IC3") (pin "13") (pinfunction "I1_13") (pintype "input"))
    )
    (net (code "72") (name "unconnected-(IC3D-O-Pad11)") (class "Default")
      (node (ref "IC3") (pin "11") (pinfunction "O_11") (pintype "output"))
    )
    (net (code "73") (name "unconnected-(X1C-KL-Pad11)") (class "Default")
      (node (ref "X1") (pin "11") (pinfunction "KL_11") (pintype "passive"))
    )
    (net (code "74") (name "unconnected-(X1D-KL-Pad12)") (class "Default")
      (node (ref "X1") (pin "12") (pinfunction "KL_12") (pintype "passive"))
    )
    (net (code "75") (name "unconnected-(X1E-KL-Pad13)") (class "Default")
      (node (ref "X1") (pin "13") (pinfunction "KL_13") (pintype "passive"))
    )
    (net (code "76") (name "unconnected-(X1F-KL-Pad14)") (class "Default")
      (node (ref "X1") (pin "14") (pinfunction "KL_14") (pintype "passive"))
    )
    (net (code "77") (name "unconnected-(X1G-KL-Pad15)") (class "Default")
      (node (ref "X1") (pin "15") (pinfunction "KL_15") (pintype "passive"))
    )
    (net (code "78") (name "unconnected-(X1H-KL-Pad16)") (class "Default")
      (node (ref "X1") (pin "16") (pinfunction "KL_16") (pintype "passive"))
    )
  )
)
